# ife18_TS_AIL_Buck.net
KiCad netlist of a schematic drawn in Altium Designer
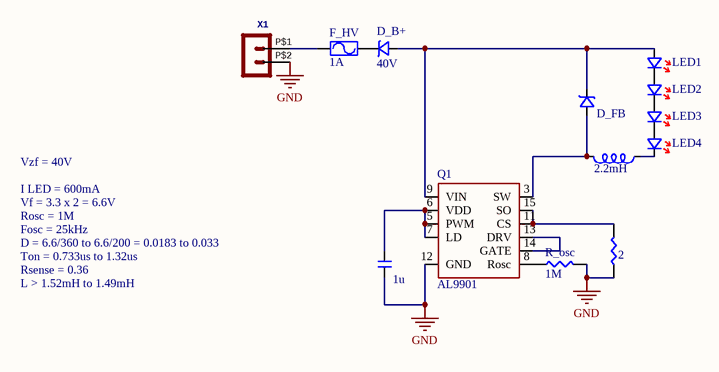
[diagram p0: ife18_TS_AIL_Buck.SchDoc]

(export (version "E")
  (design (tool "Eeschema 10.0.6"))
  (components
    (comp (ref "C_VDD")
      (value "1u")
      (footprint "CAP-0603")
      (libsource (lib "ife19_Elec_Library") (part "CAP-0603"))
    )
    (comp (ref "D_B+")
      (value "40V")
      (footprint "SMB")
      (libsource (lib "ife19_Elec_Library") (part "DIODE-SMB"))
    )
    (comp (ref "D_FB")
      (value "?")
      (footprint "SMB")
      (libsource (lib "ife19_Elec_Library") (part "DIODE-SMB"))
    )
    (comp (ref "F_HV")
      (value "1A")
      (footprint "FUSE_885")
      (libsource (lib "ife19_Elec_Library") (part "FUSE_885"))
    )
    (comp (ref "IND")
      (value "2.2mH")
      (footprint "IND-8080")
      (libsource (lib "ife19_Elec_Library") (part "IND-8080"))
    )
    (comp (ref "LED1")
      (value "LED XQA Red")
      (footprint "LED_XQARED")
      (libsource (lib "ife19_Elec_Library") (part "LED_XQARED"))
    )
    (comp (ref "LED2")
      (value "LED XQA Red")
      (footprint "LED_XQARED")
      (libsource (lib "ife19_Elec_Library") (part "LED_XQARED"))
    )
    (comp (ref "LED3")
      (value "LED XQA Red")
      (footprint "LED_XQARED")
      (libsource (lib "ife19_Elec_Library") (part "LED_XQARED"))
    )
    (comp (ref "LED4")
      (value "LED XQA Red")
      (footprint "LED_XQARED")
      (libsource (lib "ife19_Elec_Library") (part "LED_XQARED"))
    )
    (comp (ref "Q1")
      (value "AL9901")
      (footprint "SO-16")
      (libsource (lib "ife19_Elec_Library") (part "IC-SO16_AL9901_1"))
    )
    (comp (ref "R_osc")
      (value "1M")
      (footprint "RES-0603")
      (libsource (lib "ife19_Elec_Library") (part "RES-0603"))
    )
    (comp (ref "R_sense")
      (value "2")
      (footprint "RES-0603")
      (libsource (lib "ife19_Elec_Library") (part "RES-0603"))
    )
    (comp (ref "X1")
      (value "Molex - Micro-Fit 3.0 Series connector,  3.00mm (0.118\") pitch header, 2 positions.")
      (footprint "43650-0224")
      (libsource (lib "ife19_Elec_Conn_Library") (part "POS2_MF43650-0224"))
    )
  )
  (nets
    (net (code "1") (name "GND") (class "Default")
      (node (ref "C_VDD") (pin "1") (pinfunction "1_1") (pintype "passive"))
      (node (ref "Q1") (pin "12") (pinfunction "GND_12") (pintype "passive"))
      (node (ref "R_osc") (pin "2") (pinfunction "2_2") (pintype "passive"))
      (node (ref "R_sense") (pin "1") (pinfunction "1_1") (pintype "passive"))
      (node (ref "X1") (pin "P$2") (pinfunction "2_P$2") (pintype "passive"))
    )
    (net (code "2") (name "Net-(D_B+-PadK)") (class "Default")
      (node (ref "D_B+") (pin "K") (pinfunction "K_K") (pintype "passive"))
      (node (ref "F_HV") (pin "1") (pinfunction "1_1") (pintype "passive"))
    )
    (net (code "3") (name "Net-(IND-Pad1)") (class "Default")
      (node (ref "IND") (pin "1") (pinfunction "1_1") (pintype "passive"))
      (node (ref "LED4") (pin "K") (pinfunction "K_K") (pintype "passive"))
    )
    (net (code "4") (name "Net-(LED1-PadK)") (class "Default")
      (node (ref "LED1") (pin "K") (pinfunction "K_K") (pintype "passive"))
      (node (ref "LED2") (pin "A") (pinfunction "A_A") (pintype "passive"))
    )
    (net (code "5") (name "Net-(LED2-PadK)") (class "Default")
      (node (ref "LED2") (pin "K") (pinfunction "K_K") (pintype "passive"))
      (node (ref "LED3") (pin "A") (pinfunction "A_A") (pintype "passive"))
    )
    (net (code "6") (name "Net-(LED3-PadK)") (class "Default")
      (node (ref "LED3") (pin "K") (pinfunction "K_K") (pintype "passive"))
      (node (ref "LED4") (pin "A") (pinfunction "A_A") (pintype "passive"))
    )
    (net (code "7") (name "Net-(Q1-CS)") (class "Default")
      (node (ref "Q1") (pin "11") (pinfunction "CS_11") (pintype "passive"))
      (node (ref "Q1") (pin "15") (pinfunction "SO_15") (pintype "passive"))
      (node (ref "R_sense") (pin "2") (pinfunction "2_2") (pintype "passive"))
    )
    (net (code "8") (name "Net-(Q1-DRV)") (class "Default")
      (node (ref "Q1") (pin "13") (pinfunction "DRV_13") (pintype "passive"))
      (node (ref "Q1") (pin "14") (pinfunction "GATE_14") (pintype "passive"))
    )
    (net (code "9") (name "Net-(Q1-LD)") (class "Default")
      (node (ref "C_VDD") (pin "2") (pinfunction "2_2") (pintype "passive"))
      (node (ref "Q1") (pin "5") (pinfunction "PWM_5") (pintype "passive"))
      (node (ref "Q1") (pin "6") (pinfunction "VDD_6") (pintype "passive"))
      (node (ref "Q1") (pin "7") (pinfunction "LD_7") (pintype "passive"))
    )
    (net (code "10") (name "Net-(Q1-Rosc)") (class "Default")
      (node (ref "Q1") (pin "8") (pinfunction "Rosc_8") (pintype "passive"))
      (node (ref "R_osc") (pin "1") (pinfunction "1_1") (pintype "passive"))
    )
    (net (code "11") (name "Net-(Q1-SW)") (class "Default")
      (node (ref "D_FB") (pin "A") (pinfunction "A_A") (pintype "passive"))
      (node (ref "IND") (pin "2") (pinfunction "2_2") (pintype "passive"))
      (node (ref "Q1") (pin "3") (pinfunction "SW_3") (pintype "passive"))
    )
    (net (code "12") (name "Net-(Q1-VIN)") (class "Default")
      (node (ref "D_B+") (pin "A") (pinfunction "A_A") (pintype "passive"))
      (node (ref "D_FB") (pin "K") (pinfunction "K_K") (pintype "passive"))
      (node (ref "LED1") (pin "A") (pinfunction "A_A") (pintype "passive"))
      (node (ref "Q1") (pin "9") (pinfunction "VIN_9") (pintype "passive"))
    )
    (net (code "13") (name "Net-(X1-1)") (class "Default")
      (node (ref "F_HV") (pin "2") (pinfunction "2_2") (pintype "passive"))
      (node (ref "X1") (pin "P$1") (pinfunction "1_P$1") (pintype "passive"))
    )
  )
)
